# GPS_WS_NEO7M.net
KiCad netlist of a schematic drawn in Altium Designer
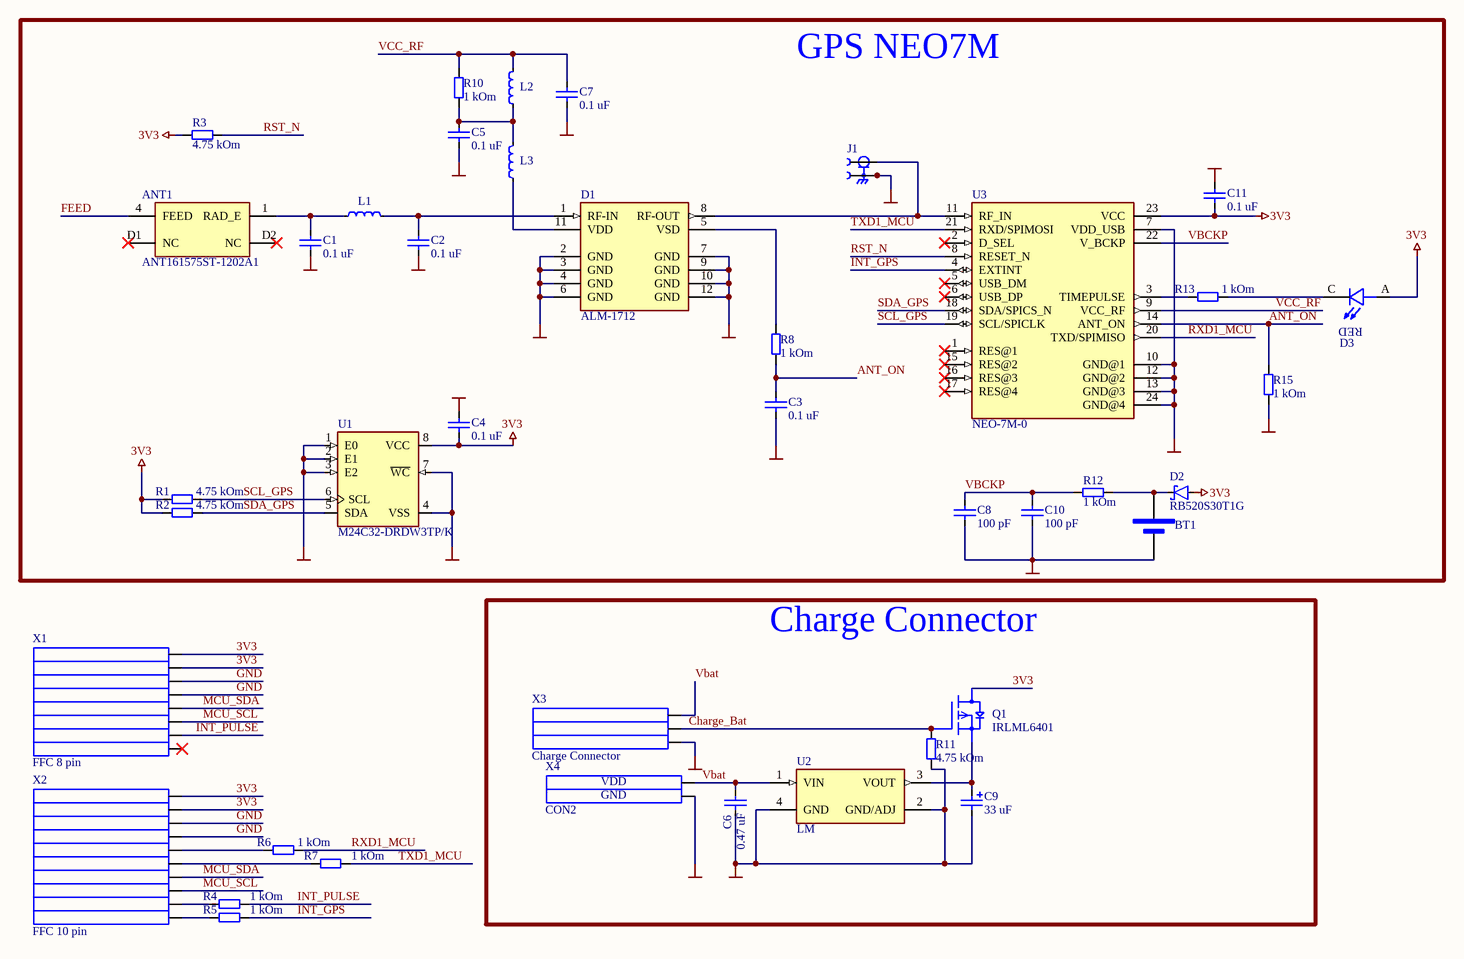
[diagram p0: GPS_WS_NEO7M.SchDoc]

(export (version "E")
  (design (tool "Eeschema 10.0.6"))
  (components
    (comp (ref "ANT1")
      (value "ANT161575ST-1202A1")
      (footprint "ANT161575ST1202A1")
      (fields
        (field (name "MANUFACTURERPARTNUMBER") "AMAN1003030ST01")
        (field (name "MANUFACTURER") "AMOTECH")
      )
      (libsource (lib "SCH_Wearing_sensor") (part "ANT161575ST-1202A1"))
    )
    (comp (ref "BT1")
      (value "ML414H_IV01E")
      (footprint "SEIKO_ML414H_IV01E")
      (description "Coin, 4.8mm 3 V Lithium Battery Rechargeable (Secondary) 1mAh")
      (fields (field (name "MP") "ML414H IV01E") (field (name "MF") "Seiko Instruments"))
      (libsource (lib "SCH_Wearing_sensor") (part "ML414H_IV01E"))
    )
    (comp (ref "C1")
      (value "0.1 uF")
      (footprint "CAPC1005X55N")
      (fields
        (field (name "MANUFACTURERPARTNUMBER") "GRM155R71H104KE14D")
        (field (name "MANUFACTURER") "muRata")
        (field (name "Comment") "STD_CAP")
        (field (name "AUTHORCREATION_COMP") "altium_lib_sch_p")
        (field (name "AUTHORMODIFICATION_COMP") "anosova")
      )
      (libsource (lib "Altium_lib") (part "STD_CAP"))
    )
    (comp (ref "C2")
      (value "0.1 uF")
      (footprint "CAPC1005X55N")
      (fields
        (field (name "MANUFACTURERPARTNUMBER") "GRM155R71H104KE14D")
        (field (name "MANUFACTURER") "muRata")
        (field (name "Comment") "STD_CAP")
        (field (name "AUTHORCREATION_COMP") "altium_lib_sch_p")
        (field (name "AUTHORMODIFICATION_COMP") "anosova")
      )
      (libsource (lib "Altium_lib") (part "STD_CAP"))
    )
    (comp (ref "C3")
      (value "0.1 uF")
      (footprint "CAPC1005X55N")
      (fields
        (field (name "MANUFACTURERPARTNUMBER") "GRM155R71H104KE14D")
        (field (name "MANUFACTURER") "muRata")
        (field (name "Comment") "STD_CAP")
        (field (name "AUTHORCREATION_COMP") "altium_lib_sch_p")
        (field (name "AUTHORMODIFICATION_COMP") "anosova")
      )
      (libsource (lib "Altium_lib") (part "STD_CAP"))
    )
    (comp (ref "C4")
      (value "0.1 uF")
      (footprint "CAPC1005X55N")
      (fields
        (field (name "MANUFACTURERPARTNUMBER") "GRM155R71H104KE14D")
        (field (name "MANUFACTURER") "muRata")
        (field (name "Comment") "STD_CAP")
        (field (name "AUTHORCREATION_COMP") "altium_lib_sch_p")
        (field (name "AUTHORMODIFICATION_COMP") "anosova")
      )
      (libsource (lib "Altium_lib") (part "STD_CAP"))
    )
    (comp (ref "C5")
      (value "0.1 uF")
      (footprint "CAPC1005X55N")
      (fields
        (field (name "MANUFACTURERPARTNUMBER") "GRM155R71H104KE14D")
        (field (name "MANUFACTURER") "muRata")
        (field (name "Comment") "STD_CAP")
        (field (name "AUTHORCREATION_COMP") "altium_lib_sch_p")
        (field (name "AUTHORMODIFICATION_COMP") "anosova")
      )
      (libsource (lib "Altium_lib") (part "STD_CAP"))
    )
    (comp (ref "C6")
      (value "0.47 uF")
      (footprint "CAPC1608X90N")
      (fields
        (field (name "MANUFACTURERPARTNUMBER") "GRM188R71A474KA61D")
        (field (name "MANUFACTURER") "muRata")
        (field (name "Comment") "STD_CAP")
      )
      (libsource (lib "Altium_lib") (part "STD_CAP"))
    )
    (comp (ref "C7")
      (value "0.1 uF")
      (footprint "CAPC1608X90N")
      (fields
        (field (name "MANUFACTURERPARTNUMBER") "C1608X7R1H104K")
        (field (name "MANUFACTURER") "TDK")
        (field (name "Comment") "STD_CAP")
        (field (name "AUTHORCREATION_COMP") "anosova")
        (field (name "AUTHORMODIFICATION_COMP") "anosova")
      )
      (libsource (lib "Altium_lib") (part "STD_CAP"))
    )
    (comp (ref "C8")
      (value "100 pF")
      (footprint "CAPC1005X55N")
      (fields
        (field (name "MANUFACTURERPARTNUMBER") "GRM1555C1H101JA01D")
        (field (name "MANUFACTURER") "muRata")
        (field (name "Comment") "STD_CAP")
        (field (name "AUTHORMODIFICATION_COMP") "anosova")
      )
      (libsource (lib "Altium_lib") (part "STD_CAP"))
    )
    (comp (ref "C9")
      (value "33 uF")
      (footprint "CAPMP3216X180N")
      (fields
        (field (name "MANUFACTURERPARTNUMBER") "T491A336K010AT")
        (field (name "MANUFACTURER") "Kemet")
        (field (name "Comment") "STD_CAP_POL")
      )
      (libsource (lib "Altium_lib") (part "STD_CAP_POL"))
    )
    (comp (ref "C10")
      (value "100 pF")
      (footprint "CAPC1005X55N")
      (fields
        (field (name "MANUFACTURERPARTNUMBER") "GRM1555C1H101JA01D")
        (field (name "MANUFACTURER") "muRata")
        (field (name "Comment") "STD_CAP")
        (field (name "AUTHORMODIFICATION_COMP") "anosova")
      )
      (libsource (lib "Altium_lib") (part "STD_CAP"))
    )
    (comp (ref "C11")
      (value "0.1 uF")
      (footprint "CAPC1005X55N")
      (fields
        (field (name "MANUFACTURERPARTNUMBER") "GRM155R71H104KE14D")
        (field (name "MANUFACTURER") "muRata")
        (field (name "Comment") "STD_CAP")
        (field (name "AUTHORCREATION_COMP") "altium_lib_sch_p")
        (field (name "AUTHORMODIFICATION_COMP") "anosova")
      )
      (libsource (lib "Altium_lib") (part "STD_CAP"))
    )
    (comp (ref "D1")
      (value "ALM-1712")
      (footprint "ALM-1712")
      (description "Sot223/Pkg 1-Amp 3.3-Volt Low Drop Out Voltage Regulatator")
      (fields (field (name "MF") "Advanced Monolithic Systems") (field (name "MP") "AMS1117-3.3"))
      (libsource (lib "SCH_Wearing_sensor") (part "ALM-1712"))
    )
    (comp (ref "D2")
      (value "RB520S30T1G")
      (footprint "SOD523:SOD523")
      (description "Diode Schottky 30 V 200mA (DC) Surface Mount SOD-523")
      (fields (field (name "MP") "1PS79SB70") (field (name "MANUFACTURER") "NXP Semiconductors"))
      (libsource (lib "SCH_Wearing_sensor") (part "RB520S30T1G"))
    )
    (comp (ref "D3")
      (value "7012X1")
      (footprint "LED_7012X1")
      (description "Red - LED Indication - Discrete 1.7V 0805 (2012 Metric)")
      (fields (field (name "MF") "VCC"))
      (libsource (lib "7012X1") (part "7012X1"))
    )
    (comp (ref "J1")
      (value "CONUFL001-SMD")
      (footprint "LINX_CONUFL001-SMD")
      (fields
        (field (name "MANUFACTURER") "TE Connectivity")
        (field (name "MANUFACTURERPARTNUMBER") "1909763-1")
      )
      (libsource (lib "SCH_Wearing_sensor") (part "CONUFL001-SMD"))
    )
    (comp (ref "L1")
      (value "STD_IND")
      (footprint "RESC1005X40N")
      (fields
        (field (name "MANUFACTURERPARTNUMBER") "LQW15AN24NG00")
        (field (name "MANUFACTURER") "muRata")
        (field (name "AUTHORCREATION_COMP") "altium_lib_sch_p")
        (field (name "AUTHORMODIFICATION_COMP") "altium_lib_sch_p")
      )
      (libsource (lib "Altium_lib") (part "STD_IND"))
    )
    (comp (ref "L2")
      (value "STD_IND")
      (footprint "RESC1005X40N")
      (fields
        (field (name "MANUFACTURERPARTNUMBER") "LQW15AN24NG00")
        (field (name "MANUFACTURER") "muRata")
        (field (name "AUTHORCREATION_COMP") "altium_lib_sch_p")
        (field (name "AUTHORMODIFICATION_COMP") "altium_lib_sch_p")
      )
      (libsource (lib "Altium_lib") (part "STD_IND"))
    )
    (comp (ref "L3")
      (value "STD_IND")
      (footprint "RESC1005X40N")
      (fields
        (field (name "MANUFACTURERPARTNUMBER") "LQW15AN24NG00")
        (field (name "MANUFACTURER") "muRata")
        (field (name "AUTHORCREATION_COMP") "altium_lib_sch_p")
        (field (name "AUTHORMODIFICATION_COMP") "altium_lib_sch_p")
      )
      (libsource (lib "Altium_lib") (part "STD_IND"))
    )
    (comp (ref "Q1")
      (value "IRLML6401")
      (footprint "SOT23")
      (description "P-Channel 12V 4.3A (Ta) 1.3W (Ta) Surface Mount Micro3â„¢/SOT-23")
      (fields (field (name "MANUFACTURER") "International Rectifier"))
      (libsource (lib "SCH_Wearing_sensor") (part "IRLML6401"))
    )
    (comp (ref "R1")
      (value "4.75 kOm")
      (footprint "RESC1005X40N")
      (fields
        (field (name "MANUFACTURERPARTNUMBER") "RC0402FR-074K75L")
        (field (name "MANUFACTURER") "Yageo")
        (field (name "Comment") "2904")
      )
      (libsource (lib "") (part "STD_RES_1"))
    )
    (comp (ref "R2")
      (value "4.75 kOm")
      (footprint "RESC1005X40N")
      (fields
        (field (name "MANUFACTURERPARTNUMBER") "RC0402FR-074K75L")
        (field (name "MANUFACTURER") "Yageo")
        (field (name "Comment") "2904")
      )
      (libsource (lib "") (part "STD_RES_1"))
    )
    (comp (ref "R3")
      (value "4.75 kOm")
      (footprint "RESC1005X40N")
      (fields
        (field (name "MANUFACTURERPARTNUMBER") "RC0402FR-074K75L")
        (field (name "MANUFACTURER") "Yageo")
        (field (name "Comment") "2904")
      )
      (libsource (lib "") (part "STD_RES_2"))
    )
    (comp (ref "R4")
      (value "1 kOm")
      (footprint "RESC1005X40N")
      (fields
        (field (name "MANUFACTURERPARTNUMBER") "RC0402FR-071K00L")
        (field (name "MANUFACTURER") "Yageo")
        (field (name "Comment") "2839")
      )
      (libsource (lib "") (part "STD_RES_1"))
    )
    (comp (ref "R5")
      (value "1 kOm")
      (footprint "RESC1005X40N")
      (fields
        (field (name "MANUFACTURERPARTNUMBER") "RC0402FR-071K00L")
        (field (name "MANUFACTURER") "Yageo")
        (field (name "Comment") "2839")
      )
      (libsource (lib "") (part "STD_RES_1"))
    )
    (comp (ref "R6")
      (value "1 kOm")
      (footprint "RESC1005X40N")
      (fields
        (field (name "MANUFACTURERPARTNUMBER") "RC0402FR-071K00L")
        (field (name "MANUFACTURER") "Yageo")
        (field (name "Comment") "2839")
      )
      (libsource (lib "") (part "STD_RES_2"))
    )
    (comp (ref "R7")
      (value "1 kOm")
      (footprint "RESC1005X40N")
      (fields
        (field (name "MANUFACTURERPARTNUMBER") "RC0402FR-071K00L")
        (field (name "MANUFACTURER") "Yageo")
        (field (name "Comment") "2839")
      )
      (libsource (lib "") (part "STD_RES_1"))
    )
    (comp (ref "R8")
      (value "1 kOm")
      (footprint "RESC1005X40N")
      (fields
        (field (name "MANUFACTURERPARTNUMBER") "RC0402FR-071K00L")
        (field (name "MANUFACTURER") "Yageo")
        (field (name "Comment") "2839")
      )
      (libsource (lib "") (part "STD_RES_2"))
    )
    (comp (ref "R10")
      (value "1 kOm")
      (footprint "RESC1005X40N")
      (fields
        (field (name "MANUFACTURERPARTNUMBER") "RC0402FR-071K00L")
        (field (name "MANUFACTURER") "Yageo")
        (field (name "Comment") "2839")
      )
      (libsource (lib "Altium_lib") (part "STD_RES"))
    )
    (comp (ref "R11")
      (value "4.75 kOm")
      (footprint "RESC1005X40N")
      (fields
        (field (name "MANUFACTURERPARTNUMBER") "RC0402FR-074K75L")
        (field (name "MANUFACTURER") "Yageo")
        (field (name "Comment") "2904")
      )
      (libsource (lib "") (part "STD_RES_3"))
    )
    (comp (ref "R12")
      (value "1 kOm")
      (footprint "RESC1005X40N")
      (fields
        (field (name "MANUFACTURERPARTNUMBER") "RC0402FR-071K00L")
        (field (name "MANUFACTURER") "Yageo")
        (field (name "Comment") "2839")
      )
      (libsource (lib "") (part "STD_RES_2"))
    )
    (comp (ref "R13")
      (value "1 kOm")
      (footprint "RESC1005X40N")
      (fields
        (field (name "MANUFACTURERPARTNUMBER") "RC0402FR-071K00L")
        (field (name "MANUFACTURER") "Yageo")
        (field (name "Comment") "2839")
      )
      (libsource (lib "") (part "STD_RES_2"))
    )
    (comp (ref "R15")
      (value "1 kOm")
      (footprint "RESC1005X40N")
      (fields
        (field (name "MANUFACTURERPARTNUMBER") "RC0402FR-071K00L")
        (field (name "MANUFACTURER") "Yageo")
        (field (name "Comment") "2839")
      )
      (libsource (lib "Altium_lib") (part "STD_RES"))
    )
    (comp (ref "U1")
      (value "M24C32-DRDW3TP/K")
      (footprint "SOP65P640X120-8N")
      (description "M24C02-F Series 2 Kb (256 x 8) 5.5 V Serial IÂ²C bus EEPROMs - TSSOP-8")
      (fields (field (name "MANUFACTURER") "STMicroelectronics"))
      (libsource (lib "SCH_Wearing_sensor") (part "M24C32-DRDW3TP/K"))
    )
    (comp (ref "U2")
      (value "LM")
      (footprint "SOT229P700X180-4N")
      (description "Sot223/Pkg 1-Amp 3.3-Volt Low Drop Out Voltage Regulatator")
      (fields (field (name "MF") "Advanced Monolithic Systems") (field (name "MP") "AMS1117-3.3"))
      (libsource (lib "SCH_Wearing_sensor") (part "LM"))
    )
    (comp (ref "U3")
      (value "NEO-7M-0")
      (footprint "XCVR_NEO-7M-0")
      (description "NEO-7 RF Receiver GLONASS, GNSS, GPS 1.575GHz -161dBm")
      (fields (field (name "MF") "U-Blox America"))
      (libsource (lib "SCH_Wearing_sensor") (part "NEO-7M-0"))
    )
    (comp (ref "X1")
      (value "FFC 8 pin")
      (footprint "Charge Connector")
      (description "FFC connector 8 pin")
      (libsource (lib "SCH_Wearing_sensor") (part "FFC 8 pin"))
    )
    (comp (ref "X2")
      (value "FFC 10 pin")
      (footprint "SAMTEC_ZF5S-10-01-T-WT")
      (description "FFC connector 8 pin")
      (libsource (lib "SCH_Wearing_sensor") (part "FFC 10 pin"))
    )
    (comp (ref "X3")
      (value "Charge Connector")
      (footprint "POGO PINS")
      (description "Выводы под плату зарядки")
      (libsource (lib "SCH_Wearing_sensor") (part "Charge Connector"))
    )
    (comp (ref "X4")
      (value "CON2")
      (footprint "CON2")
      (description "Коннектор двухконтактный")
      (fields (field (name "MANUFACTURERPARTNUMBER") "LP401230") (field (name "MANUFACTURER") "Robiton"))
      (libsource (lib "SCH_Wearing_sensor") (part "CON2"))
    )
  )
  (nets
    (net (code "1") (name "/ANT_ON") (class "Default")
      (node (ref "C3") (pin "1") (pinfunction "1_1") (pintype "passive"))
      (node (ref "R15") (pin "1") (pinfunction "1_1") (pintype "passive"))
      (node (ref "R8") (pin "2") (pinfunction "2_2") (pintype "passive"))
      (node (ref "U3") (pin "14") (pinfunction "ANT_ON_14") (pintype "output"))
    )
    (net (code "2") (name "/Charge_Bat") (class "Default")
      (node (ref "Q1") (pin "1") (pinfunction "G_1") (pintype "passive"))
      (node (ref "R11") (pin "2") (pinfunction "2_2") (pintype "passive"))
      (node (ref "X3") (pin "2") (pintype "passive"))
    )
    (net (code "3") (name "/FEED") (class "Default")
      (node (ref "ANT1") (pin "4") (pinfunction "FEED_4") (pintype "passive"))
    )
    (net (code "4") (name "/INT_GPS") (class "Default")
      (node (ref "R5") (pin "2") (pinfunction "2_2") (pintype "passive"))
      (node (ref "U3") (pin "4") (pinfunction "EXTINT_4") (pintype "bidirectional"))
    )
    (net (code "5") (name "/INT_PULSE") (class "Default")
      (node (ref "R4") (pin "2") (pinfunction "2_2") (pintype "passive"))
      (node (ref "X1") (pin "7") (pintype "passive"))
    )
    (net (code "6") (name "/MCU_SCL") (class "Default")
      (node (ref "X1") (pin "6") (pintype "passive"))
      (node (ref "X2") (pin "8") (pintype "passive"))
    )
    (net (code "7") (name "/MCU_SDA") (class "Default")
      (node (ref "X1") (pin "5") (pintype "passive"))
      (node (ref "X2") (pin "7") (pintype "passive"))
    )
    (net (code "8") (name "/RST_N") (class "Default")
      (node (ref "R3") (pin "1") (pinfunction "1_1") (pintype "passive"))
      (node (ref "U3") (pin "8") (pinfunction "RESET_N_8") (pintype "input"))
    )
    (net (code "9") (name "/RXD1_MCU") (class "Default")
      (node (ref "R6") (pin "1") (pinfunction "1_1") (pintype "passive"))
      (node (ref "U3") (pin "20") (pinfunction "TXD/SPIMISO_20") (pintype "output"))
    )
    (net (code "10") (name "/SCL_GPS") (class "Default")
      (node (ref "R1") (pin "2") (pinfunction "2_2") (pintype "passive"))
      (node (ref "U1") (pin "6") (pinfunction "SCL_6") (pintype "input"))
      (node (ref "U3") (pin "19") (pinfunction "SCL/SPICLK_19") (pintype "bidirectional"))
    )
    (net (code "11") (name "/SDA_GPS") (class "Default")
      (node (ref "R2") (pin "2") (pinfunction "2_2") (pintype "passive"))
      (node (ref "U1") (pin "5") (pinfunction "SDA_5") (pintype "bidirectional"))
      (node (ref "U3") (pin "18") (pinfunction "SDA/SPICS_N_18") (pintype "bidirectional"))
    )
    (net (code "12") (name "/TXD1_MCU") (class "Default")
      (node (ref "R7") (pin "2") (pinfunction "2_2") (pintype "passive"))
      (node (ref "U3") (pin "21") (pinfunction "RXD/SPIMOSI_21") (pintype "input"))
    )
    (net (code "13") (name "/VBCKP") (class "Default")
      (node (ref "C10") (pin "1") (pinfunction "1_1") (pintype "passive"))
      (node (ref "C8") (pin "1") (pinfunction "1_1") (pintype "passive"))
      (node (ref "R12") (pin "2") (pinfunction "2_2") (pintype "passive"))
      (node (ref "U3") (pin "22") (pinfunction "V_BCKP_22") (pintype "power_in"))
    )
    (net (code "14") (name "/VCC_RF") (class "Default")
      (node (ref "C7") (pin "1") (pinfunction "1_1") (pintype "passive"))
      (node (ref "L2") (pin "2") (pinfunction "2_2") (pintype "passive"))
      (node (ref "R10") (pin "1") (pinfunction "1_1") (pintype "passive"))
      (node (ref "U3") (pin "9") (pinfunction "VCC_RF_9") (pintype "output"))
    )
    (net (code "15") (name "/Vbat") (class "Default")
      (node (ref "C6") (pin "1") (pinfunction "1_1") (pintype "passive"))
      (node (ref "U2") (pin "1") (pinfunction "VIN_1") (pintype "input"))
      (node (ref "X3") (pin "1") (pintype "passive"))
      (node (ref "X4") (pin "1") (pintype "passive"))
    )
    (net (code "16") (name "3V3") (class "Default")
      (node (ref "C11") (pin "2") (pinfunction "2_2") (pintype "passive"))
      (node (ref "C4") (pin "2") (pinfunction "2_2") (pintype "passive"))
      (node (ref "D2") (pin "2") (pinfunction "A_2") (pintype "passive"))
      (node (ref "D3") (pin "A") (pinfunction "A_A") (pintype "passive"))
      (node (ref "Q1") (pin "3") (pinfunction "D_3") (pintype "passive"))
      (node (ref "R1") (pin "1") (pinfunction "1_1") (pintype "passive"))
      (node (ref "R2") (pin "1") (pinfunction "1_1") (pintype "passive"))
      (node (ref "R3") (pin "2") (pinfunction "2_2") (pintype "passive"))
      (node (ref "U1") (pin "8") (pinfunction "VCC_8") (pintype "power_in"))
      (node (ref "U3") (pin "23") (pinfunction "VCC_23") (pintype "power_in"))
      (node (ref "X1") (pin "1") (pintype "passive"))
      (node (ref "X1") (pin "2") (pintype "passive"))
      (node (ref "X2") (pin "1") (pintype "passive"))
      (node (ref "X2") (pin "2") (pintype "passive"))
    )
    (net (code "17") (name "GND") (class "Default")
      (node (ref "BT1") (pin "2") (pinfunction "NEG_2") (pintype "passive"))
      (node (ref "C1") (pin "2") (pinfunction "2_2") (pintype "passive"))
      (node (ref "C10") (pin "2") (pinfunction "2_2") (pintype "passive"))
      (node (ref "C11") (pin "1") (pinfunction "1_1") (pintype "passive"))
      (node (ref "C2") (pin "2") (pinfunction "2_2") (pintype "passive"))
      (node (ref "C3") (pin "2") (pinfunction "2_2") (pintype "passive"))
      (node (ref "C4") (pin "1") (pinfunction "1_1") (pintype "passive"))
      (node (ref "C5") (pin "2") (pinfunction "2_2") (pintype "passive"))
      (node (ref "C6") (pin "2") (pinfunction "2_2") (pintype "passive"))
      (node (ref "C7") (pin "2") (pinfunction "2_2") (pintype "passive"))
      (node (ref "C8") (pin "2") (pinfunction "2_2") (pintype "passive"))
      (node (ref "C9") (pin "2") (pinfunction "2_2") (pintype "passive"))
      (node (ref "D1") (pin "10") (pinfunction "GND_10") (pintype "passive"))
      (node (ref "D1") (pin "12") (pinfunction "GND_12") (pintype "passive"))
      (node (ref "D1") (pin "2") (pinfunction "GND_2") (pintype "passive"))
      (node (ref "D1") (pin "3") (pinfunction "GND_3") (pintype "passive"))
      (node (ref "D1") (pin "4") (pinfunction "GND_4") (pintype "passive"))
      (node (ref "D1") (pin "6") (pinfunction "GND_6") (pintype "passive"))
      (node (ref "D1") (pin "7") (pinfunction "GND_7") (pintype "passive"))
      (node (ref "D1") (pin "9") (pinfunction "GND_9") (pintype "passive"))
      (node (ref "J1") (pin "2") (pinfunction "2_2") (pintype "passive"))
      (node (ref "J1") (pin "3") (pinfunction "2_3") (pintype "passive"))
      (node (ref "R11") (pin "1") (pinfunction "1_1") (pintype "passive"))
      (node (ref "R15") (pin "2") (pinfunction "2_2") (pintype "passive"))
      (node (ref "U1") (pin "1") (pinfunction "E0_1") (pintype "input"))
      (node (ref "U1") (pin "2") (pinfunction "E1_2") (pintype "input"))
      (node (ref "U1") (pin "3") (pinfunction "E2_3") (pintype "input"))
      (node (ref "U1") (pin "4") (pinfunction "VSS_4") (pintype "power_in"))
      (node (ref "U1") (pin "7") (pinfunction "~{WC}_7") (pintype "input"))
      (node (ref "U2") (pin "2") (pinfunction "GND/ADJ_2") (pintype "power_in"))
      (node (ref "U2") (pin "4") (pinfunction "GND_4") (pintype "passive"))
      (node (ref "U3") (pin "10") (pinfunction "GND@1_10") (pintype "power_in"))
      (node (ref "U3") (pin "12") (pinfunction "GND@2_12") (pintype "power_in"))
      (node (ref "U3") (pin "13") (pinfunction "GND@3_13") (pintype "power_in"))
      (node (ref "U3") (pin "24") (pinfunction "GND@4_24") (pintype "power_in"))
      (node (ref "U3") (pin "7") (pinfunction "VDD_USB_7") (pintype "power_in"))
      (node (ref "X1") (pin "3") (pintype "passive"))
      (node (ref "X1") (pin "4") (pintype "passive"))
      (node (ref "X2") (pin "3") (pintype "passive"))
      (node (ref "X2") (pin "4") (pintype "passive"))
      (node (ref "X3") (pin "3") (pintype "passive"))
      (node (ref "X4") (pin "2") (pintype "passive"))
    )
    (net (code "18") (name "Net-(ANT1-RAD_E)") (class "Default")
      (node (ref "ANT1") (pin "1") (pinfunction "RAD_E_1") (pintype "passive"))
      (node (ref "C1") (pin "1") (pinfunction "1_1") (pintype "passive"))
      (node (ref "L1") (pin "1") (pinfunction "1_1") (pintype "passive"))
    )
    (net (code "19") (name "Net-(BT1-POS)") (class "Default")
      (node (ref "BT1") (pin "1") (pinfunction "POS_1") (pintype "passive"))
      (node (ref "D2") (pin "1") (pinfunction "K_1") (pintype "passive"))
      (node (ref "R12") (pin "1") (pinfunction "1_1") (pintype "passive"))
    )
    (net (code "20") (name "Net-(C5-Pad1)") (class "Default")
      (node (ref "C5") (pin "1") (pinfunction "1_1") (pintype "passive"))
      (node (ref "L2") (pin "1") (pinfunction "1_1") (pintype "passive"))
      (node (ref "L3") (pin "2") (pinfunction "2_2") (pintype "passive"))
      (node (ref "R10") (pin "2") (pinfunction "2_2") (pintype "passive"))
    )
    (net (code "21") (name "Net-(D1-RF-IN)") (class "Default")
      (node (ref "C2") (pin "1") (pinfunction "1_1") (pintype "passive"))
      (node (ref "D1") (pin "1") (pinfunction "RF-IN_1") (pintype "input"))
      (node (ref "L1") (pin "2") (pinfunction "2_2") (pintype "passive"))
    )
    (net (code "22") (name "Net-(D1-RF-OUT)") (class "Default")
      (node (ref "D1") (pin "8") (pinfunction "RF-OUT_8") (pintype "output"))
      (node (ref "J1") (pin "1") (pinfunction "1_1") (pintype "passive"))
      (node (ref "U3") (pin "11") (pinfunction "RF_IN_11") (pintype "input"))
    )
    (net (code "23") (name "Net-(D1-VDD)") (class "Default")
      (node (ref "D1") (pin "11") (pinfunction "VDD_11") (pintype "passive"))
      (node (ref "L3") (pin "1") (pinfunction "1_1") (pintype "passive"))
    )
    (net (code "24") (name "Net-(D1-VSD)") (class "Default")
      (node (ref "D1") (pin "5") (pinfunction "VSD_5") (pintype "power_in"))
      (node (ref "R8") (pin "1") (pinfunction "1_1") (pintype "passive"))
    )
    (net (code "25") (name "Net-(D3-PadC)") (class "Default")
      (node (ref "D3") (pin "C") (pinfunction "C_C") (pintype "passive"))
      (node (ref "R13") (pin "1") (pinfunction "1_1") (pintype "passive"))
    )
    (net (code "26") (name "Net-(Q1-S)") (class "Default")
      (node (ref "C9") (pin "1") (pinfunction "1_1") (pintype "passive"))
      (node (ref "Q1") (pin "2") (pinfunction "S_2") (pintype "passive"))
      (node (ref "U2") (pin "3") (pinfunction "VOUT_3") (pintype "output"))
    )
    (net (code "27") (name "Net-(R4-Pad1)") (class "Default")
      (node (ref "R4") (pin "1") (pinfunction "1_1") (pintype "passive"))
      (node (ref "X2") (pin "9") (pintype "passive"))
    )
    (net (code "28") (name "Net-(R5-Pad1)") (class "Default")
      (node (ref "R5") (pin "1") (pinfunction "1_1") (pintype "passive"))
      (node (ref "X2") (pin "10") (pintype "passive"))
    )
    (net (code "29") (name "Net-(R6-Pad2)") (class "Default")
      (node (ref "R6") (pin "2") (pinfunction "2_2") (pintype "passive"))
      (node (ref "X2") (pin "5") (pintype "passive"))
    )
    (net (code "30") (name "Net-(R7-Pad1)") (class "Default")
      (node (ref "R7") (pin "1") (pinfunction "1_1") (pintype "passive"))
      (node (ref "X2") (pin "6") (pintype "passive"))
    )
    (net (code "31") (name "Net-(U3-TIMEPULSE)") (class "Default")
      (node (ref "R13") (pin "2") (pinfunction "2_2") (pintype "passive"))
      (node (ref "U3") (pin "3") (pinfunction "TIMEPULSE_3") (pintype "output"))
    )
    (net (code "32") (name "unconnected-(ANT1-NC-PadD1)") (class "Default")
      (node (ref "ANT1") (pin "D1") (pinfunction "NC_D1") (pintype "passive+no_connect"))
    )
    (net (code "33") (name "unconnected-(ANT1-NC-PadD2)") (class "Default")
      (node (ref "ANT1") (pin "D2") (pinfunction "NC_D2") (pintype "passive+no_connect"))
    )
    (net (code "34") (name "unconnected-(U3-D_SEL-Pad2)") (class "Default")
      (node (ref "U3") (pin "2") (pinfunction "D_SEL_2") (pintype "input+no_connect"))
    )
    (net (code "35") (name "unconnected-(U3-RES@1-Pad1)") (class "Default")
      (node (ref "U3") (pin "1") (pinfunction "RES@1_1") (pintype "input+no_connect"))
    )
    (net (code "36") (name "unconnected-(U3-RES@2-Pad15)") (class "Default")
      (node (ref "U3") (pin "15") (pinfunction "RES@2_15") (pintype "input+no_connect"))
    )
    (net (code "37") (name "unconnected-(U3-RES@3-Pad16)") (class "Default")
      (node (ref "U3") (pin "16") (pinfunction "RES@3_16") (pintype "input+no_connect"))
    )
    (net (code "38") (name "unconnected-(U3-RES@4-Pad17)") (class "Default")
      (node (ref "U3") (pin "17") (pinfunction "RES@4_17") (pintype "input+no_connect"))
    )
    (net (code "39") (name "unconnected-(U3-USB_DM-Pad5)") (class "Default")
      (node (ref "U3") (pin "5") (pinfunction "USB_DM_5") (pintype "bidirectional+no_connect"))
    )
    (net (code "40") (name "unconnected-(U3-USB_DP-Pad6)") (class "Default")
      (node (ref "U3") (pin "6") (pinfunction "USB_DP_6") (pintype "bidirectional+no_connect"))
    )
    (net (code "41") (name "unconnected-(X1-Pad8)") (class "Default")
      (node (ref "X1") (pin "8") (pintype "passive+no_connect"))
    )
  )
)
